# SCHE_B555.net
KiCad netlist of a schematic drawn in Altium Designer
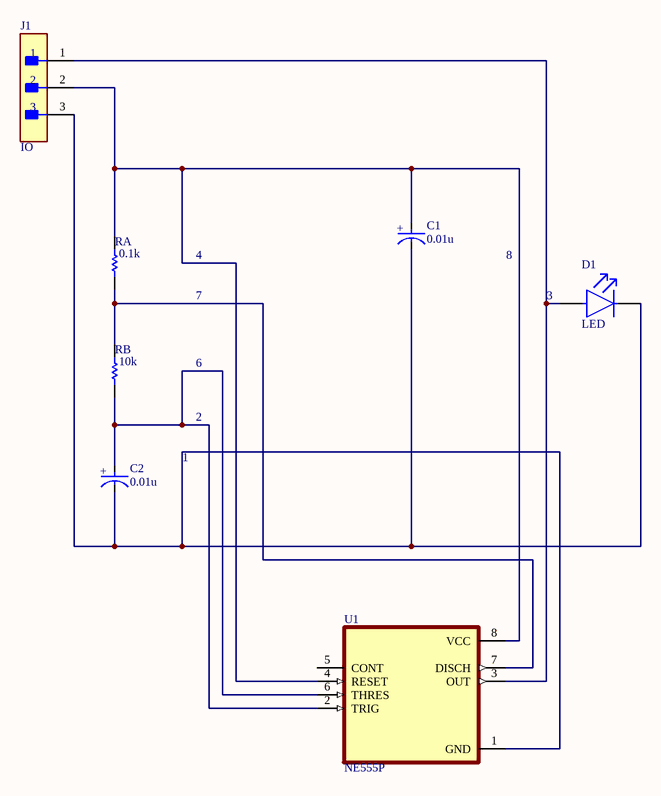
[diagram p0: SCHE_B555.SchDoc]

(export (version "E")
  (design (tool "Eeschema 10.0.6"))
  (components
    (comp (ref "C1")
      (value "0.01u")
      (footprint "FP-RAD-TH-D_16_0_5-L_31_5-MFG")
      (fields (field (name "TOLERANCE") "20%") (field (name "VOLTAGE") "50V"))
      (libsource (lib "Altium Content Vault") (part "203bc49f2ac43e59fd269a8c329ed05"))
    )
    (comp (ref "C2")
      (value "0.01u")
      (footprint "FP-RAD-TH-D_16_0_5-L_31_5-MFG")
      (fields (field (name "TOLERANCE") "20%") (field (name "VOLTAGE") "50V"))
      (libsource (lib "Altium Content Vault") (part "203bc49f2ac43e59fd269a8c329ed05"))
    )
    (comp (ref "D1")
      (value "LED")
      (footprint "FP-HLMP-1301-MFG")
      (fields
        (field (name "MANUFACTURER PART NUMBER") "HLMP-1301")
        (field (name "OCTOPART") "https://octopart.com/hlmp-1301-broadcom-71130345")
        (field (name "MANUFACTURER") "Broadcom")
      )
      (libsource (lib "Altium Content Vault") (part "8706943c75ba83719d021d2fdc84c58"))
    )
    (comp (ref "J1")
      (value "IO")
      (footprint "FP-22-28-4030-MFG")
      (description "{1 to OUT, 2 to V_CC, 3 to GNC}")
      (fields
        (field (name "MANUFACTURER PART NUMBER") "22-28-4030")
        (field (name "OCTOPART") "https://octopart.com/0022284030-molex-10476094")
      )
      (libsource (lib "Altium Content Vault") (part "0d3f023dd272f625e17a2be33dea85f"))
    )
    (comp (ref "RA")
      (value "0.1k")
      (footprint "RESA60-630X240")
      (fields (field (name "TOLERANCE") "20%"))
      (libsource (lib "Altium Content Vault") (part "RES-2"))
    )
    (comp (ref "RB")
      (value "10k")
      (footprint "RESA60-630X240")
      (fields (field (name "TOLERANCE") "20%"))
      (libsource (lib "Altium Content Vault") (part "RES-2"))
    )
    (comp (ref "U1")
      (value "NE555P")
      (footprint "DIP794W45P254L959H508Q8")
      (libsource (lib "NE555P") (part "NE555P"))
    )
  )
  (nets
    (net (code "1") (name "Net-(C1-A)") (class "Default")
      (node (ref "C1") (pin "2") (pinfunction "A_2") (pintype "passive"))
      (node (ref "J1") (pin "2") (pinfunction "2_2") (pintype "passive"))
      (node (ref "RA") (pin "1") (pinfunction "1_1") (pintype "passive"))
      (node (ref "U1") (pin "4") (pinfunction "RESET_4") (pintype "input"))
      (node (ref "U1") (pin "8") (pinfunction "VCC_8") (pintype "power_in"))
    )
    (net (code "2") (name "Net-(C1-C)") (class "Default")
      (node (ref "C1") (pin "1") (pinfunction "C_1") (pintype "passive"))
      (node (ref "C2") (pin "1") (pinfunction "C_1") (pintype "passive"))
      (node (ref "D1") (pin "1") (pinfunction "C_1") (pintype "passive"))
      (node (ref "J1") (pin "3") (pinfunction "3_3") (pintype "passive"))
      (node (ref "U1") (pin "1") (pinfunction "GND_1") (pintype "power_in"))
    )
    (net (code "3") (name "Net-(C2-A)") (class "Default")
      (node (ref "C2") (pin "2") (pinfunction "A_2") (pintype "passive"))
      (node (ref "RB") (pin "2") (pinfunction "2_2") (pintype "passive"))
      (node (ref "U1") (pin "2") (pinfunction "TRIG_2") (pintype "input"))
      (node (ref "U1") (pin "6") (pinfunction "THRES_6") (pintype "input"))
    )
    (net (code "4") (name "Net-(D1-A)") (class "Default")
      (node (ref "D1") (pin "2") (pinfunction "A_2") (pintype "passive"))
      (node (ref "J1") (pin "1") (pinfunction "1_1") (pintype "passive"))
      (node (ref "U1") (pin "3") (pinfunction "OUT_3") (pintype "output"))
    )
    (net (code "5") (name "Net-(U1-DISCH)") (class "Default")
      (node (ref "RA") (pin "2") (pinfunction "2_2") (pintype "passive"))
      (node (ref "RB") (pin "1") (pinfunction "1_1") (pintype "passive"))
      (node (ref "U1") (pin "7") (pinfunction "DISCH_7") (pintype "output"))
    )
    (net (code "6") (name "unconnected-(U1-CONT-Pad5)") (class "Default")
      (node (ref "U1") (pin "5") (pinfunction "CONT_5") (pintype "passive"))
    )
  )
)
